# Vector_Mini_ST_2.net
KiCad netlist of a schematic drawn in Altium Designer
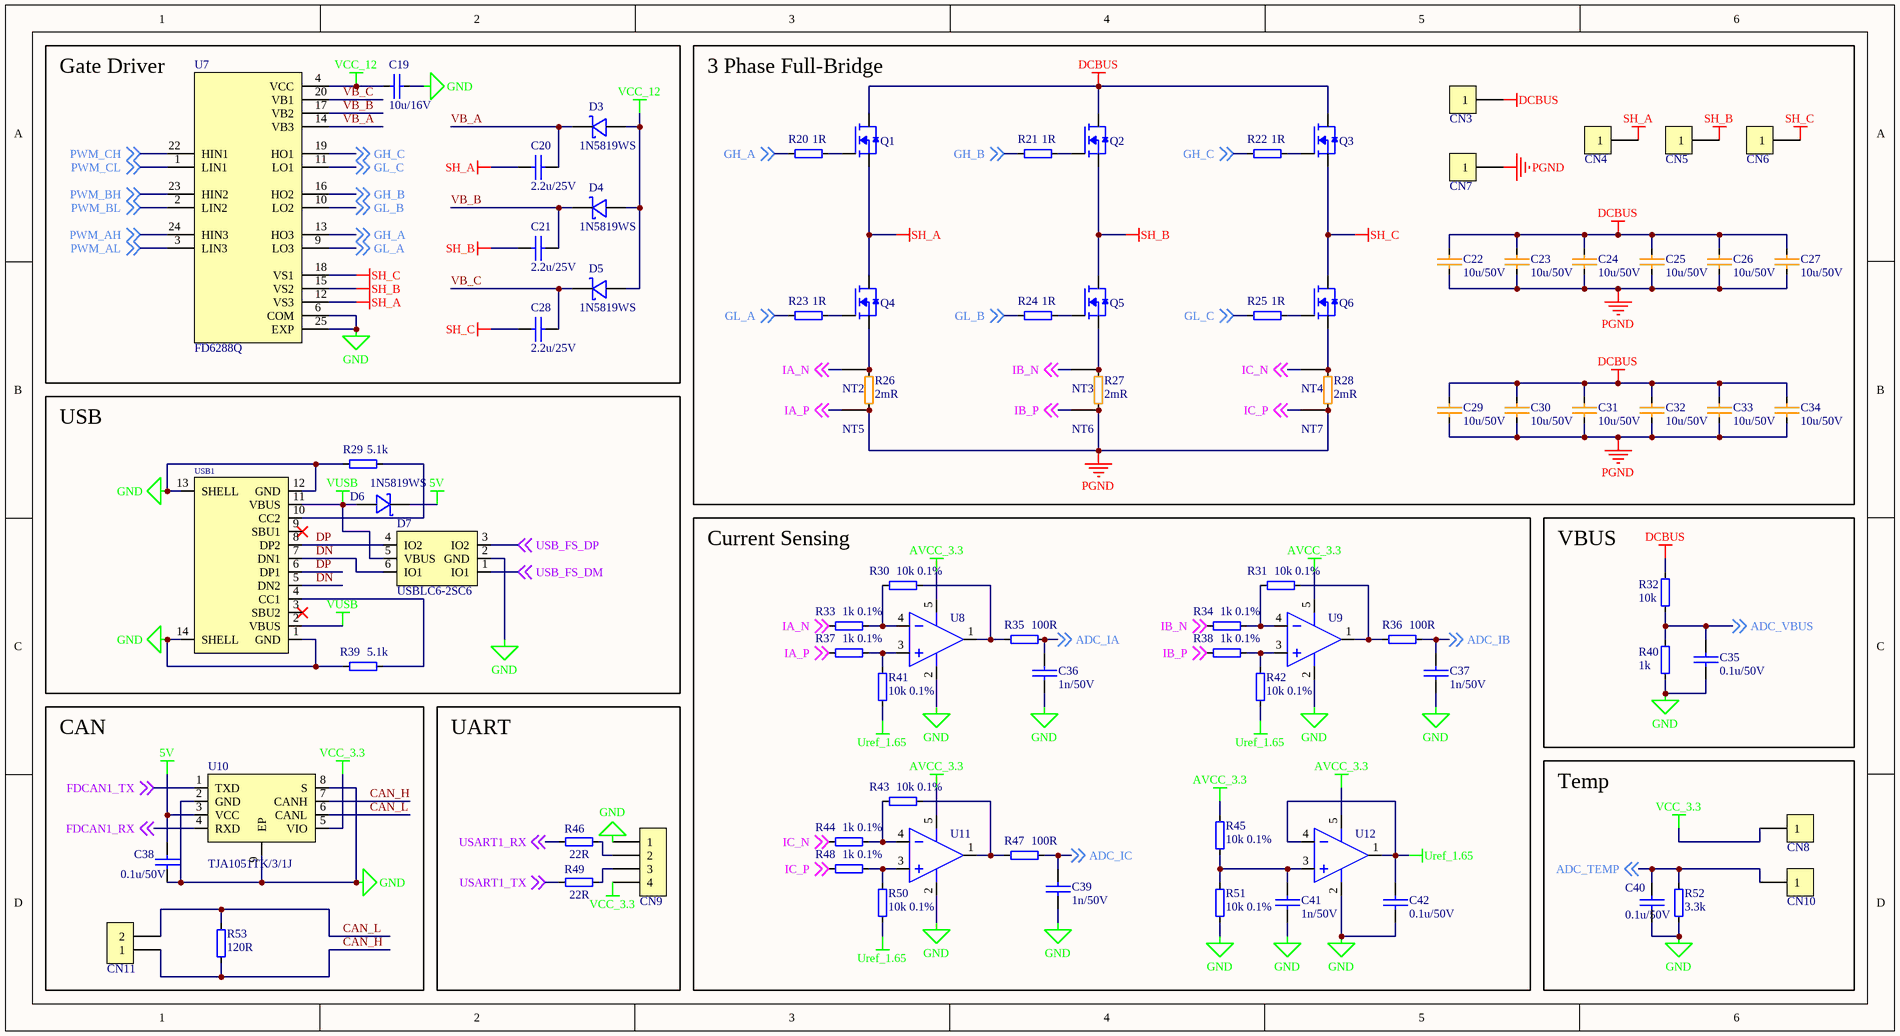
[diagram p0: Vector_Mini_ST_2.SchDoc]

(export (version "E")
  (design (tool "Eeschema 10.0.6"))
  (components
    (comp (ref "C19")
      (value "10u/16V")
      (footprint "C0603_S")
      (description "贴片电容")
      (libsource (lib "") (part "CAP_1"))
    )
    (comp (ref "C20")
      (value "2.2u/25V")
      (footprint "C0603_S")
      (description "贴片电容")
      (libsource (lib "Controller") (part "CAP"))
    )
    (comp (ref "C21")
      (value "2.2u/25V")
      (footprint "C0603_S")
      (description "贴片电容")
      (libsource (lib "Controller") (part "CAP"))
    )
    (comp (ref "C22")
      (value "10u/50V")
      (footprint "C1206_S")
      (description "1206贴片电容")
      (libsource (lib "Capacitor") (part "C1206"))
    )
    (comp (ref "C23")
      (value "10u/50V")
      (footprint "C1206_S")
      (description "1206贴片电容")
      (libsource (lib "Capacitor") (part "C1206"))
    )
    (comp (ref "C24")
      (value "10u/50V")
      (footprint "C1206_S")
      (description "1206贴片电容")
      (libsource (lib "Capacitor") (part "C1206"))
    )
    (comp (ref "C25")
      (value "10u/50V")
      (footprint "C1206_S")
      (description "1206贴片电容")
      (libsource (lib "Capacitor") (part "C1206"))
    )
    (comp (ref "C26")
      (value "10u/50V")
      (footprint "C1206_S")
      (description "1206贴片电容")
      (libsource (lib "Capacitor") (part "C1206"))
    )
    (comp (ref "C27")
      (value "10u/50V")
      (footprint "C1206_S")
      (description "1206贴片电容")
      (libsource (lib "Capacitor") (part "C1206"))
    )
    (comp (ref "C28")
      (value "2.2u/25V")
      (footprint "C0603_S")
      (description "贴片电容")
      (libsource (lib "Controller") (part "CAP"))
    )
    (comp (ref "C29")
      (value "10u/50V")
      (footprint "C1206_S")
      (description "1206贴片电容")
      (libsource (lib "Capacitor") (part "C1206"))
    )
    (comp (ref "C30")
      (value "10u/50V")
      (footprint "C1206_S")
      (description "1206贴片电容")
      (libsource (lib "Capacitor") (part "C1206"))
    )
    (comp (ref "C31")
      (value "10u/50V")
      (footprint "C1206_S")
      (description "1206贴片电容")
      (libsource (lib "Capacitor") (part "C1206"))
    )
    (comp (ref "C32")
      (value "10u/50V")
      (footprint "C1206_S")
      (description "1206贴片电容")
      (libsource (lib "Capacitor") (part "C1206"))
    )
    (comp (ref "C33")
      (value "10u/50V")
      (footprint "C1206_S")
      (description "1206贴片电容")
      (libsource (lib "Capacitor") (part "C1206"))
    )
    (comp (ref "C34")
      (value "10u/50V")
      (footprint "C1206_S")
      (description "1206贴片电容")
      (libsource (lib "Capacitor") (part "C1206"))
    )
    (comp (ref "C35")
      (value "0.1u/50V")
      (footprint "C0603_S")
      (description "贴片电容")
      (libsource (lib "Controller") (part "CAP"))
    )
    (comp (ref "C36")
      (value "1n/50V")
      (footprint "C0603_S")
      (description "贴片电容")
      (libsource (lib "Controller") (part "CAP"))
    )
    (comp (ref "C37")
      (value "1n/50V")
      (footprint "C0603_S")
      (description "贴片电容")
      (libsource (lib "Controller") (part "CAP"))
    )
    (comp (ref "C38")
      (value "0.1u/50V")
      (footprint "C0603_S")
      (description "贴片电容")
      (libsource (lib "Controller") (part "CAP"))
    )
    (comp (ref "C39")
      (value "1n/50V")
      (footprint "C0603_S")
      (description "贴片电容")
      (libsource (lib "Controller") (part "CAP"))
    )
    (comp (ref "C40")
      (value "0.1u/50V")
      (footprint "C0603_S")
      (description "贴片电容")
      (libsource (lib "Controller") (part "CAP"))
    )
    (comp (ref "C41")
      (value "1n/50V")
      (footprint "C0603_S")
      (description "贴片电容")
      (libsource (lib "Controller") (part "CAP"))
    )
    (comp (ref "C42")
      (value "0.1u/50V")
      (footprint "C0603_S")
      (description "贴片电容")
      (libsource (lib "Controller") (part "CAP"))
    )
    (comp (ref "CN3") (value "PAD 5*4") (footprint "PAD 5*4") (libsource (lib "Connector") (part "PAD 5*4")))
    (comp (ref "CN4") (value "PAD 5*4") (footprint "PAD 5*4") (libsource (lib "Connector") (part "PAD 5*4")))
    (comp (ref "CN5") (value "PAD 5*4") (footprint "PAD 5*4") (libsource (lib "Connector") (part "PAD 5*4")))
    (comp (ref "CN6") (value "PAD 5*4") (footprint "PAD 5*4") (libsource (lib "Connector") (part "PAD 5*4")))
    (comp (ref "CN7") (value "PAD 5*4") (footprint "PAD 5*4") (libsource (lib "Connector") (part "PAD 5*4")))
    (comp (ref "CN8") (value "PAD 1*1") (footprint "PAD 1*1") (libsource (lib "Connector") (part "PAD 1*1")))
    (comp (ref "CN9")
      (value "GH1.25-4P")
      (footprint "GH1.25-WS-4P")
      (libsource (lib "Controller") (part "GH1.25-4P"))
    )
    (comp (ref "CN10") (value "PAD 1*1") (footprint "PAD 1*1") (libsource (lib "Connector") (part "PAD 1*1")))
    (comp (ref "CN11")
      (value "GH1.25-2P")
      (footprint "GH1.25-WS-2P")
      (libsource (lib "Controller") (part "GH1.25-2P"))
    )
    (comp (ref "D3")
      (value "1N5819WS")
      (footprint "SOD-323")
      (description "肖特基二极管")
      (fields (field (name "MANUFACTURER") "Hottech(合科泰)"))
      (libsource (lib "Controller") (part "1N5819WS"))
    )
    (comp (ref "D4")
      (value "1N5819WS")
      (footprint "SOD-323")
      (description "肖特基二极管")
      (fields (field (name "MANUFACTURER") "Hottech(合科泰)"))
      (libsource (lib "Controller") (part "1N5819WS"))
    )
    (comp (ref "D5")
      (value "1N5819WS")
      (footprint "SOD-323")
      (description "肖特基二极管")
      (fields (field (name "MANUFACTURER") "Hottech(合科泰)"))
      (libsource (lib "Controller") (part "1N5819WS"))
    )
    (comp (ref "D6")
      (value "1N5819WS")
      (footprint "SOD-323")
      (description "肖特基二极管")
      (fields (field (name "MANUFACTURER") "Hottech(合科泰)"))
      (libsource (lib "Controller") (part "1N5819WS"))
    )
    (comp (ref "D7")
      (value "USBLC6-2SC6")
      (footprint "SOT-23-6")
      (description "USB 2.0高速接口的ESD保护")
      (libsource (lib "Controller") (part "USBLC6-2SC6"))
    )
    (comp (ref "NT2")
      (value "NetTie_6mil")
      (footprint "Nettie6mil")
      (libsource (lib "Connector") (part "NetTie_6mil"))
    )
    (comp (ref "NT3")
      (value "NetTie_6mil")
      (footprint "Nettie6mil")
      (libsource (lib "Connector") (part "NetTie_6mil"))
    )
    (comp (ref "NT4")
      (value "NetTie_6mil")
      (footprint "Nettie6mil")
      (libsource (lib "Connector") (part "NetTie_6mil"))
    )
    (comp (ref "NT5")
      (value "NetTie_6mil")
      (footprint "Nettie6mil")
      (libsource (lib "Connector") (part "NetTie_6mil"))
    )
    (comp (ref "NT6")
      (value "NetTie_6mil")
      (footprint "Nettie6mil")
      (libsource (lib "Connector") (part "NetTie_6mil"))
    )
    (comp (ref "NT7")
      (value "NetTie_6mil")
      (footprint "Nettie6mil")
      (libsource (lib "Connector") (part "NetTie_6mil"))
    )
    (comp (ref "Q1")
      (value "CSD18540Q5B")
      (footprint "VSON-8")
      (fields (field (name "MF") "Texas Instruments"))
      (libsource (lib "Transistor") (part "CSD18540Q5B"))
    )
    (comp (ref "Q2")
      (value "CSD18540Q5B")
      (footprint "VSON-8")
      (fields (field (name "MF") "Texas Instruments"))
      (libsource (lib "Transistor") (part "CSD18540Q5B"))
    )
    (comp (ref "Q3")
      (value "CSD18540Q5B")
      (footprint "VSON-8")
      (fields (field (name "MF") "Texas Instruments"))
      (libsource (lib "Transistor") (part "CSD18540Q5B"))
    )
    (comp (ref "Q4")
      (value "CSD18540Q5B")
      (footprint "VSON-8")
      (fields (field (name "MF") "Texas Instruments"))
      (libsource (lib "Transistor") (part "CSD18540Q5B"))
    )
    (comp (ref "Q5")
      (value "CSD18540Q5B")
      (footprint "VSON-8")
      (fields (field (name "MF") "Texas Instruments"))
      (libsource (lib "Transistor") (part "CSD18540Q5B"))
    )
    (comp (ref "Q6")
      (value "CSD18540Q5B")
      (footprint "VSON-8")
      (fields (field (name "MF") "Texas Instruments"))
      (libsource (lib "Transistor") (part "CSD18540Q5B"))
    )
    (comp (ref "R20")
      (value "1R")
      (footprint "R0603_S")
      (description "贴片电阻")
      (libsource (lib "Controller") (part "RES"))
    )
    (comp (ref "R21")
      (value "1R")
      (footprint "R0603_S")
      (description "贴片电阻")
      (libsource (lib "Controller") (part "RES"))
    )
    (comp (ref "R22")
      (value "1R")
      (footprint "R0603_S")
      (description "贴片电阻")
      (libsource (lib "Controller") (part "RES"))
    )
    (comp (ref "R23")
      (value "1R")
      (footprint "R0603_S")
      (description "贴片电阻")
      (libsource (lib "Controller") (part "RES"))
    )
    (comp (ref "R24")
      (value "1R")
      (footprint "R0603_S")
      (description "贴片电阻")
      (libsource (lib "Controller") (part "RES"))
    )
    (comp (ref "R25")
      (value "1R")
      (footprint "R0603_S")
      (description "贴片电阻")
      (libsource (lib "Controller") (part "RES"))
    )
    (comp (ref "R26")
      (value "2mR")
      (footprint "R2512_S")
      (description "2512贴片电阻")
      (libsource (lib "Resistor") (part "R2512"))
    )
    (comp (ref "R27")
      (value "2mR")
      (footprint "R2512_S")
      (description "2512贴片电阻")
      (libsource (lib "Resistor") (part "R2512"))
    )
    (comp (ref "R28")
      (value "2mR")
      (footprint "R2512_S")
      (description "2512贴片电阻")
      (libsource (lib "Resistor") (part "R2512"))
    )
    (comp (ref "R29")
      (value "5.1k")
      (footprint "R0603_S")
      (description "贴片电阻")
      (libsource (lib "Controller") (part "RES"))
    )
    (comp (ref "R30")
      (value "10k 0.1%")
      (footprint "R0603_S")
      (description "贴片电阻")
      (libsource (lib "Controller") (part "RES"))
    )
    (comp (ref "R31")
      (value "10k 0.1%")
      (footprint "R0603_S")
      (description "贴片电阻")
      (libsource (lib "Controller") (part "RES"))
    )
    (comp (ref "R32")
      (value "10k")
      (footprint "R0603_S")
      (description "贴片电阻")
      (libsource (lib "Controller") (part "RES"))
    )
    (comp (ref "R33")
      (value "1k 0.1%")
      (footprint "R0603_S")
      (description "贴片电阻")
      (libsource (lib "Controller") (part "RES"))
    )
    (comp (ref "R34")
      (value "1k 0.1%")
      (footprint "R0603_S")
      (description "贴片电阻")
      (libsource (lib "Controller") (part "RES"))
    )
    (comp (ref "R35")
      (value "100R")
      (footprint "R0603_S")
      (description "贴片电阻")
      (libsource (lib "Controller") (part "RES"))
    )
    (comp (ref "R36")
      (value "100R")
      (footprint "R0603_S")
      (description "贴片电阻")
      (libsource (lib "Controller") (part "RES"))
    )
    (comp (ref "R37")
      (value "1k 0.1%")
      (footprint "R0603_S")
      (description "贴片电阻")
      (libsource (lib "Controller") (part "RES"))
    )
    (comp (ref "R38")
      (value "1k 0.1%")
      (footprint "R0603_S")
      (description "贴片电阻")
      (libsource (lib "Controller") (part "RES"))
    )
    (comp (ref "R39")
      (value "5.1k")
      (footprint "R0603_S")
      (description "贴片电阻")
      (libsource (lib "Controller") (part "RES"))
    )
    (comp (ref "R40")
      (value "1k")
      (footprint "R0603_S")
      (description "贴片电阻")
      (libsource (lib "Controller") (part "RES"))
    )
    (comp (ref "R41")
      (value "10k 0.1%")
      (footprint "R0603_S")
      (description "贴片电阻")
      (libsource (lib "Controller") (part "RES"))
    )
    (comp (ref "R42")
      (value "10k 0.1%")
      (footprint "R0603_S")
      (description "贴片电阻")
      (libsource (lib "Controller") (part "RES"))
    )
    (comp (ref "R43")
      (value "10k 0.1%")
      (footprint "R0603_S")
      (description "贴片电阻")
      (libsource (lib "Controller") (part "RES"))
    )
    (comp (ref "R44")
      (value "1k 0.1%")
      (footprint "R0603_S")
      (description "贴片电阻")
      (libsource (lib "Controller") (part "RES"))
    )
    (comp (ref "R45")
      (value "10k 0.1%")
      (footprint "R0603_S")
      (description "贴片电阻")
      (libsource (lib "Controller") (part "RES"))
    )
    (comp (ref "R46")
      (value "22R")
      (footprint "R0603_S")
      (description "贴片电阻")
      (libsource (lib "Controller") (part "RES"))
    )
    (comp (ref "R47")
      (value "100R")
      (footprint "R0603_S")
      (description "贴片电阻")
      (libsource (lib "Controller") (part "RES"))
    )
    (comp (ref "R48")
      (value "1k 0.1%")
      (footprint "R0603_S")
      (description "贴片电阻")
      (libsource (lib "Controller") (part "RES"))
    )
    (comp (ref "R49")
      (value "22R")
      (footprint "R0603_S")
      (description "贴片电阻")
      (libsource (lib "Controller") (part "RES"))
    )
    (comp (ref "R50")
      (value "10k 0.1%")
      (footprint "R0603_S")
      (description "贴片电阻")
      (libsource (lib "Controller") (part "RES"))
    )
    (comp (ref "R51")
      (value "10k 0.1%")
      (footprint "R0603_S")
      (description "贴片电阻")
      (libsource (lib "Controller") (part "RES"))
    )
    (comp (ref "R52")
      (value "3.3k")
      (footprint "R0603_S")
      (description "贴片电阻")
      (libsource (lib "Controller") (part "RES"))
    )
    (comp (ref "R53")
      (value "120R")
      (footprint "R0603_S")
      (description "贴片电阻")
      (libsource (lib "Controller") (part "RES"))
    )
    (comp (ref "U7")
      (value "FD6288Q")
      (footprint "QFN-24")
      (description "三相栅极驱动")
      (fields (field (name "MF") "{'manufacturer': u'Fortior Tech'}"))
      (libsource (lib "Power Regulate") (part "FD6288Q"))
    )
    (comp (ref "U8") (value "RS721XF") (footprint "SOT-23-5") (libsource (lib "Amplifier") (part "RS721XF")))
    (comp (ref "U9") (value "RS721XF") (footprint "SOT-23-5") (libsource (lib "Amplifier") (part "RS721XF")))
    (comp (ref "U10")
      (value "TJA1051TK/3/1J")
      (footprint "VDFN-8")
      (fields (field (name "MANUFACTURER") "NXP(恩智浦)") (field (name "MANUFACTURER PART") "TJA1051T/1J"))
      (libsource (lib "Interface") (part "TJA1051TK/3/1J"))
    )
    (comp (ref "U11") (value "RS721XF") (footprint "SOT-23-5") (libsource (lib "Amplifier") (part "RS721XF")))
    (comp (ref "U12") (value "RS721XF") (footprint "SOT-23-5") (libsource (lib "Amplifier") (part "RS721XF")))
    (comp (ref "USB1")
      (value "TYPEC-WS-16P")
      (footprint "TYPEC-WS-16P")
      (fields
        (field (name "MANUFACTURER") "SHOU HAN(首韩)")
        (field (name "MANUFACTURER PART") "TYPE-C 16PIN 2MD(073)")
      )
      (libsource (lib "USB") (part "TYPEC-WS-16P"))
    )
  )
  (nets
    (net (code "1") (name "/CAN_H") (class "Default")
      (node (ref "CN11") (pin "1") (pinfunction "1_1") (pintype "passive"))
      (node (ref "R53") (pin "1") (pinfunction "1_1") (pintype "passive"))
      (node (ref "U10") (pin "7") (pinfunction "CANH_7") (pintype "passive"))
    )
    (net (code "2") (name "/CAN_L") (class "Default")
      (node (ref "CN11") (pin "2") (pinfunction "2_2") (pintype "passive"))
      (node (ref "R53") (pin "2") (pinfunction "2_2") (pintype "passive"))
      (node (ref "U10") (pin "6") (pinfunction "CANL_6") (pintype "passive"))
    )
    (net (code "3") (name "/DN") (class "Default")
      (node (ref "D7") (pin "6") (pinfunction "IO1_6") (pintype "passive"))
      (node (ref "USB1") (pin "5") (pinfunction "DN2_5") (pintype "passive"))
      (node (ref "USB1") (pin "7") (pinfunction "DN1_7") (pintype "passive"))
    )
    (net (code "4") (name "/DP") (class "Default")
      (node (ref "D7") (pin "4") (pinfunction "IO2_4") (pintype "passive"))
      (node (ref "USB1") (pin "6") (pinfunction "DP1_6") (pintype "passive"))
      (node (ref "USB1") (pin "8") (pinfunction "DP2_8") (pintype "passive"))
    )
    (net (code "5") (name "/VB_A") (class "Default")
      (node (ref "C20") (pin "2") (pinfunction "2_2") (pintype "passive"))
      (node (ref "D3") (pin "1") (pinfunction "K_1") (pintype "passive"))
      (node (ref "U7") (pin "14") (pinfunction "VB3_14") (pintype "passive"))
    )
    (net (code "6") (name "/VB_B") (class "Default")
      (node (ref "C21") (pin "2") (pinfunction "2_2") (pintype "passive"))
      (node (ref "D4") (pin "1") (pinfunction "K_1") (pintype "passive"))
      (node (ref "U7") (pin "17") (pinfunction "VB2_17") (pintype "passive"))
    )
    (net (code "7") (name "/VB_C") (class "Default")
      (node (ref "C28") (pin "2") (pinfunction "2_2") (pintype "passive"))
      (node (ref "D5") (pin "1") (pinfunction "K_1") (pintype "passive"))
      (node (ref "U7") (pin "20") (pinfunction "VB1_20") (pintype "passive"))
    )
    (net (code "8") (name "5V") (class "Default")
      (node (ref "C38") (pin "1") (pinfunction "1_1") (pintype "passive"))
      (node (ref "D6") (pin "1") (pinfunction "K_1") (pintype "passive"))
      (node (ref "U10") (pin "3") (pinfunction "VCC_3") (pintype "passive"))
    )
    (net (code "9") (name "ADC_IA") (class "Default")
      (node (ref "C36") (pin "2") (pinfunction "2_2") (pintype "passive"))
      (node (ref "R35") (pin "2") (pinfunction "2_2") (pintype "passive"))
    )
    (net (code "10") (name "ADC_IB") (class "Default")
      (node (ref "C37") (pin "2") (pinfunction "2_2") (pintype "passive"))
      (node (ref "R36") (pin "2") (pinfunction "2_2") (pintype "passive"))
    )
    (net (code "11") (name "ADC_IC") (class "Default")
      (node (ref "C39") (pin "2") (pinfunction "2_2") (pintype "passive"))
      (node (ref "R47") (pin "2") (pinfunction "2_2") (pintype "passive"))
    )
    (net (code "12") (name "ADC_TEMP") (class "Default")
      (node (ref "C40") (pin "1") (pinfunction "1_1") (pintype "passive"))
      (node (ref "CN10") (pin "1") (pinfunction "1_1") (pintype "passive"))
      (node (ref "R52") (pin "2") (pinfunction "2_2") (pintype "passive"))
    )
    (net (code "13") (name "ADC_VBUS") (class "Default")
      (node (ref "C35") (pin "2") (pinfunction "2_2") (pintype "passive"))
      (node (ref "R32") (pin "1") (pinfunction "1_1") (pintype "passive"))
      (node (ref "R40") (pin "2") (pinfunction "2_2") (pintype "passive"))
    )
    (net (code "14") (name "AVCC_3.3") (class "Default")
      (node (ref "R45") (pin "2") (pinfunction "2_2") (pintype "passive"))
      (node (ref "U11") (pin "5") (pinfunction "V+_5") (pintype "passive"))
      (node (ref "U12") (pin "5") (pinfunction "V+_5") (pintype "passive"))
      (node (ref "U8") (pin "5") (pinfunction "V+_5") (pintype "passive"))
      (node (ref "U9") (pin "5") (pinfunction "V+_5") (pintype "passive"))
    )
    (net (code "15") (name "DCBUS") (class "Default")
      (node (ref "C22") (pin "1") (pinfunction "1_1") (pintype "passive"))
      (node (ref "C23") (pin "1") (pinfunction "1_1") (pintype "passive"))
      (node (ref "C24") (pin "1") (pinfunction "1_1") (pintype "passive"))
      (node (ref "C25") (pin "1") (pinfunction "1_1") (pintype "passive"))
      (node (ref "C26") (pin "1") (pinfunction "1_1") (pintype "passive"))
      (node (ref "C27") (pin "1") (pinfunction "1_1") (pintype "passive"))
      (node (ref "C29") (pin "1") (pinfunction "1_1") (pintype "passive"))
      (node (ref "C30") (pin "1") (pinfunction "1_1") (pintype "passive"))
      (node (ref "C31") (pin "1") (pinfunction "1_1") (pintype "passive"))
      (node (ref "C32") (pin "1") (pinfunction "1_1") (pintype "passive"))
      (node (ref "C33") (pin "1") (pinfunction "1_1") (pintype "passive"))
      (node (ref "C34") (pin "1") (pinfunction "1_1") (pintype "passive"))
      (node (ref "CN3") (pin "1") (pinfunction "1_1") (pintype "passive"))
      (node (ref "Q1") (pin "3") (pinfunction "D_3") (pintype "passive"))
      (node (ref "Q2") (pin "3") (pinfunction "D_3") (pintype "passive"))
      (node (ref "Q3") (pin "3") (pinfunction "D_3") (pintype "passive"))
      (node (ref "R32") (pin "2") (pinfunction "2_2") (pintype "passive"))
    )
    (net (code "16") (name "FDCAN1_RX") (class "Default")
      (node (ref "U10") (pin "4") (pinfunction "RXD_4") (pintype "passive"))
    )
    (net (code "17") (name "FDCAN1_TX") (class "Default")
      (node (ref "U10") (pin "1") (pinfunction "TXD_1") (pintype "passive"))
    )
    (net (code "18") (name "GH_A") (class "Default")
      (node (ref "R20") (pin "1") (pinfunction "1_1") (pintype "passive"))
      (node (ref "U7") (pin "13") (pinfunction "HO3_13") (pintype "passive"))
    )
    (net (code "19") (name "GH_B") (class "Default")
      (node (ref "R21") (pin "1") (pinfunction "1_1") (pintype "passive"))
      (node (ref "U7") (pin "16") (pinfunction "HO2_16") (pintype "passive"))
    )
    (net (code "20") (name "GH_C") (class "Default")
      (node (ref "R22") (pin "1") (pinfunction "1_1") (pintype "passive"))
      (node (ref "U7") (pin "19") (pinfunction "HO1_19") (pintype "passive"))
    )
    (net (code "21") (name "GL_A") (class "Default")
      (node (ref "R23") (pin "1") (pinfunction "1_1") (pintype "passive"))
      (node (ref "U7") (pin "9") (pinfunction "LO3_9") (pintype "passive"))
    )
    (net (code "22") (name "GL_B") (class "Default")
      (node (ref "R24") (pin "1") (pinfunction "1_1") (pintype "passive"))
      (node (ref "U7") (pin "10") (pinfunction "LO2_10") (pintype "passive"))
    )
    (net (code "23") (name "GL_C") (class "Default")
      (node (ref "R25") (pin "1") (pinfunction "1_1") (pintype "passive"))
      (node (ref "U7") (pin "11") (pinfunction "LO1_11") (pintype "passive"))
    )
    (net (code "24") (name "GND") (class "Default")
      (node (ref "C19") (pin "2") (pinfunction "2_2") (pintype "passive"))
      (node (ref "C35") (pin "1") (pinfunction "1_1") (pintype "passive"))
      (node (ref "C36") (pin "1") (pinfunction "1_1") (pintype "passive"))
      (node (ref "C37") (pin "1") (pinfunction "1_1") (pintype "passive"))
      (node (ref "C38") (pin "2") (pinfunction "2_2") (pintype "passive"))
      (node (ref "C39") (pin "1") (pinfunction "1_1") (pintype "passive"))
      (node (ref "C40") (pin "2") (pinfunction "2_2") (pintype "passive"))
      (node (ref "C41") (pin "1") (pinfunction "1_1") (pintype "passive"))
      (node (ref "C42") (pin "1") (pinfunction "1_1") (pintype "passive"))
      (node (ref "CN9") (pin "1") (pinfunction "1_1") (pintype "passive"))
      (node (ref "D7") (pin "2") (pinfunction "GND_2") (pintype "passive"))
      (node (ref "R29") (pin "1") (pinfunction "1_1") (pintype "passive"))
      (node (ref "R39") (pin "1") (pinfunction "1_1") (pintype "passive"))
      (node (ref "R40") (pin "1") (pinfunction "1_1") (pintype "passive"))
      (node (ref "R51") (pin "1") (pinfunction "1_1") (pintype "passive"))
      (node (ref "R52") (pin "1") (pinfunction "1_1") (pintype "passive"))
      (node (ref "U10") (pin "2") (pinfunction "GND_2") (pintype "passive"))
      (node (ref "U10") (pin "8") (pinfunction "S_8") (pintype "passive"))
      (node (ref "U10") (pin "9") (pinfunction "EP_9") (pintype "passive"))
      (node (ref "U11") (pin "2") (pinfunction "V-_2") (pintype "passive"))
      (node (ref "U12") (pin "2") (pinfunction "V-_2") (pintype "passive"))
      (node (ref "U7") (pin "25") (pinfunction "EXP_25") (pintype "passive"))
      (node (ref "U7") (pin "6") (pinfunction "COM_6") (pintype "passive"))
      (node (ref "U8") (pin "2") (pinfunction "V-_2") (pintype "passive"))
      (node (ref "U9") (pin "2") (pinfunction "V-_2") (pintype "passive"))
      (node (ref "USB1") (pin "1") (pinfunction "GND_1") (pintype "passive"))
      (node (ref "USB1") (pin "12") (pinfunction "GND_12") (pintype "passive"))
      (node (ref "USB1") (pin "13") (pinfunction "SHELL_13") (pintype "passive"))
      (node (ref "USB1") (pin "14") (pinfunction "SHELL_14") (pintype "passive"))
    )
    (net (code "25") (name "IA_N") (class "Default")
      (node (ref "NT2") (pin "1") (pintype "passive"))
      (node (ref "R33") (pin "1") (pinfunction "1_1") (pintype "passive"))
    )
    (net (code "26") (name "IA_P") (class "Default")
      (node (ref "NT5") (pin "1") (pintype "passive"))
      (node (ref "R37") (pin "1") (pinfunction "1_1") (pintype "passive"))
    )
    (net (code "27") (name "IB_N") (class "Default")
      (node (ref "NT3") (pin "1") (pintype "passive"))
      (node (ref "R34") (pin "1") (pinfunction "1_1") (pintype "passive"))
    )
    (net (code "28") (name "IB_P") (class "Default")
      (node (ref "NT6") (pin "1") (pintype "passive"))
      (node (ref "R38") (pin "1") (pinfunction "1_1") (pintype "passive"))
    )
    (net (code "29") (name "IC_N") (class "Default")
      (node (ref "NT4") (pin "1") (pintype "passive"))
      (node (ref "R44") (pin "1") (pinfunction "1_1") (pintype "passive"))
    )
    (net (code "30") (name "IC_P") (class "Default")
      (node (ref "NT7") (pin "1") (pintype "passive"))
      (node (ref "R48") (pin "1") (pinfunction "1_1") (pintype "passive"))
    )
    (net (code "31") (name "Net-(CN9-Pad2)") (class "Default")
      (node (ref "CN9") (pin "2") (pinfunction "2_2") (pintype "passive"))
      (node (ref "R46") (pin "2") (pinfunction "2_2") (pintype "passive"))
    )
    (net (code "32") (name "Net-(CN9-Pad3)") (class "Default")
      (node (ref "CN9") (pin "3") (pinfunction "3_3") (pintype "passive"))
      (node (ref "R49") (pin "2") (pinfunction "2_2") (pintype "passive"))
    )
    (net (code "33") (name "Net-(Q1-G)") (class "Default")
      (node (ref "Q1") (pin "2") (pinfunction "G_2") (pintype "passive"))
      (node (ref "R20") (pin "2") (pinfunction "2_2") (pintype "passive"))
    )
    (net (code "34") (name "Net-(Q2-G)") (class "Default")
      (node (ref "Q2") (pin "2") (pinfunction "G_2") (pintype "passive"))
      (node (ref "R21") (pin "2") (pinfunction "2_2") (pintype "passive"))
    )
    (net (code "35") (name "Net-(Q3-G)") (class "Default")
      (node (ref "Q3") (pin "2") (pinfunction "G_2") (pintype "passive"))
      (node (ref "R22") (pin "2") (pinfunction "2_2") (pintype "passive"))
    )
    (net (code "36") (name "Net-(Q4-G)") (class "Default")
      (node (ref "Q4") (pin "2") (pinfunction "G_2") (pintype "passive"))
      (node (ref "R23") (pin "2") (pinfunction "2_2") (pintype "passive"))
    )
    (net (code "37") (name "Net-(Q4-S)") (class "Default")
      (node (ref "NT2") (pin "2") (pinfunction "2_2") (pintype "passive"))
      (node (ref "Q4") (pin "1") (pinfunction "S_1") (pintype "passive"))
      (node (ref "R26") (pin "2") (pinfunction "2_2") (pintype "passive"))
    )
    (net (code "38") (name "Net-(Q5-G)") (class "Default")
      (node (ref "Q5") (pin "2") (pinfunction "G_2") (pintype "passive"))
      (node (ref "R24") (pin "2") (pinfunction "2_2") (pintype "passive"))
    )
    (net (code "39") (name "Net-(Q5-S)") (class "Default")
      (node (ref "NT3") (pin "2") (pinfunction "2_2") (pintype "passive"))
      (node (ref "Q5") (pin "1") (pinfunction "S_1") (pintype "passive"))
      (node (ref "R27") (pin "2") (pinfunction "2_2") (pintype "passive"))
    )
    (net (code "40") (name "Net-(Q6-G)") (class "Default")
      (node (ref "Q6") (pin "2") (pinfunction "G_2") (pintype "passive"))
      (node (ref "R25") (pin "2") (pinfunction "2_2") (pintype "passive"))
    )
    (net (code "41") (name "Net-(Q6-S)") (class "Default")
      (node (ref "NT4") (pin "2") (pinfunction "2_2") (pintype "passive"))
      (node (ref "Q6") (pin "1") (pinfunction "S_1") (pintype "passive"))
      (node (ref "R28") (pin "2") (pinfunction "2_2") (pintype "passive"))
    )
    (net (code "42") (name "Net-(U8-+IN)") (class "Default")
      (node (ref "R37") (pin "2") (pinfunction "2_2") (pintype "passive"))
      (node (ref "R41") (pin "2") (pinfunction "2_2") (pintype "passive"))
      (node (ref "U8") (pin "3") (pinfunction "+IN_3") (pintype "passive"))
    )
    (net (code "43") (name "Net-(U8--IN)") (class "Default")
      (node (ref "R30") (pin "1") (pinfunction "1_1") (pintype "passive"))
      (node (ref "R33") (pin "2") (pinfunction "2_2") (pintype "passive"))
      (node (ref "U8") (pin "4") (pinfunction "-IN_4") (pintype "passive"))
    )
    (net (code "44") (name "Net-(U8-OUT)") (class "Default")
      (node (ref "R30") (pin "2") (pinfunction "2_2") (pintype "passive"))
      (node (ref "R35") (pin "1") (pinfunction "1_1") (pintype "passive"))
      (node (ref "U8") (pin "1") (pinfunction "OUT_1") (pintype "passive"))
    )
    (net (code "45") (name "Net-(U9-+IN)") (class "Default")
      (node (ref "R38") (pin "2") (pinfunction "2_2") (pintype "passive"))
      (node (ref "R42") (pin "2") (pinfunction "2_2") (pintype "passive"))
      (node (ref "U9") (pin "3") (pinfunction "+IN_3") (pintype "passive"))
    )
    (net (code "46") (name "Net-(U9--IN)") (class "Default")
      (node (ref "R31") (pin "1") (pinfunction "1_1") (pintype "passive"))
      (node (ref "R34") (pin "2") (pinfunction "2_2") (pintype "passive"))
      (node (ref "U9") (pin "4") (pinfunction "-IN_4") (pintype "passive"))
    )
    (net (code "47") (name "Net-(U9-OUT)") (class "Default")
      (node (ref "R31") (pin "2") (pinfunction "2_2") (pintype "passive"))
      (node (ref "R36") (pin "1") (pinfunction "1_1") (pintype "passive"))
      (node (ref "U9") (pin "1") (pinfunction "OUT_1") (pintype "passive"))
    )
    (net (code "48") (name "Net-(U11-+IN)") (class "Default")
      (node (ref "R48") (pin "2") (pinfunction "2_2") (pintype "passive"))
      (node (ref "R50") (pin "2") (pinfunction "2_2") (pintype "passive"))
      (node (ref "U11") (pin "3") (pinfunction "+IN_3") (pintype "passive"))
    )
    (net (code "49") (name "Net-(U11--IN)") (class "Default")
      (node (ref "R43") (pin "1") (pinfunction "1_1") (pintype "passive"))
      (node (ref "R44") (pin "2") (pinfunction "2_2") (pintype "passive"))
      (node (ref "U11") (pin "4") (pinfunction "-IN_4") (pintype "passive"))
    )
    (net (code "50") (name "Net-(U11-OUT)") (class "Default")
      (node (ref "R43") (pin "2") (pinfunction "2_2") (pintype "passive"))
      (node (ref "R47") (pin "1") (pinfunction "1_1") (pintype "passive"))
      (node (ref "U11") (pin "1") (pinfunction "OUT_1") (pintype "passive"))
    )
    (net (code "51") (name "Net-(U12-+IN)") (class "Default")
      (node (ref "C41") (pin "2") (pinfunction "2_2") (pintype "passive"))
      (node (ref "R45") (pin "1") (pinfunction "1_1") (pintype "passive"))
      (node (ref "R51") (pin "2") (pinfunction "2_2") (pintype "passive"))
      (node (ref "U12") (pin "3") (pinfunction "+IN_3") (pintype "passive"))
    )
    (net (code "52") (name "Net-(USB1-CC1)") (class "Default")
      (node (ref "R39") (pin "2") (pinfunction "2_2") (pintype "passive"))
      (node (ref "USB1") (pin "4") (pinfunction "CC1_4") (pintype "passive"))
    )
    (net (code "53") (name "Net-(USB1-CC2)") (class "Default")
      (node (ref "R29") (pin "2") (pinfunction "2_2") (pintype "passive"))
      (node (ref "USB1") (pin "10") (pinfunction "CC2_10") (pintype "passive"))
    )
    (net (code "54") (name "PGND") (class "Default")
      (node (ref "C22") (pin "2") (pinfunction "2_2") (pintype "passive"))
      (node (ref "C23") (pin "2") (pinfunction "2_2") (pintype "passive"))
      (node (ref "C24") (pin "2") (pinfunction "2_2") (pintype "passive"))
      (node (ref "C25") (pin "2") (pinfunction "2_2") (pintype "passive"))
      (node (ref "C26") (pin "2") (pinfunction "2_2") (pintype "passive"))
      (node (ref "C27") (pin "2") (pinfunction "2_2") (pintype "passive"))
      (node (ref "C29") (pin "2") (pinfunction "2_2") (pintype "passive"))
      (node (ref "C30") (pin "2") (pinfunction "2_2") (pintype "passive"))
      (node (ref "C31") (pin "2") (pinfunction "2_2") (pintype "passive"))
      (node (ref "C32") (pin "2") (pinfunction "2_2") (pintype "passive"))
      (node (ref "C33") (pin "2") (pinfunction "2_2") (pintype "passive"))
      (node (ref "C34") (pin "2") (pinfunction "2_2") (pintype "passive"))
      (node (ref "CN7") (pin "1") (pinfunction "1_1") (pintype "passive"))
      (node (ref "NT5") (pin "2") (pinfunction "2_2") (pintype "passive"))
      (node (ref "NT6") (pin "2") (pinfunction "2_2") (pintype "passive"))
      (node (ref "NT7") (pin "2") (pinfunction "2_2") (pintype "passive"))
      (node (ref "R26") (pin "1") (pinfunction "1_1") (pintype "passive"))
      (node (ref "R27") (pin "1") (pinfunction "1_1") (pintype "passive"))
      (node (ref "R28") (pin "1") (pinfunction "1_1") (pintype "passive"))
    )
    (net (code "55") (name "PWM_AH") (class "Default")
      (node (ref "U7") (pin "24") (pinfunction "HIN3_24") (pintype "passive"))
    )
    (net (code "56") (name "PWM_AL") (class "Default")
      (node (ref "U7") (pin "3") (pinfunction "LIN3_3") (pintype "passive"))
    )
    (net (code "57") (name "PWM_BH") (class "Default")
      (node (ref "U7") (pin "23") (pinfunction "HIN2_23") (pintype "passive"))
    )
    (net (code "58") (name "PWM_BL") (class "Default")
      (node (ref "U7") (pin "2") (pinfunction "LIN2_2") (pintype "passive"))
    )
    (net (code "59") (name "PWM_CH") (class "Default")
      (node (ref "U7") (pin "22") (pinfunction "HIN1_22") (pintype "passive"))
    )
    (net (code "60") (name "PWM_CL") (class "Default")
      (node (ref "U7") (pin "1") (pinfunction "LIN1_1") (pintype "passive"))
    )
    (net (code "61") (name "SH_A") (class "Default")
      (node (ref "C20") (pin "1") (pinfunction "1_1") (pintype "passive"))
      (node (ref "CN4") (pin "1") (pinfunction "1_1") (pintype "passive"))
      (node (ref "Q1") (pin "1") (pinfunction "S_1") (pintype "passive"))
      (node (ref "Q4") (pin "3") (pinfunction "D_3") (pintype "passive"))
      (node (ref "U7") (pin "12") (pinfunction "VS3_12") (pintype "passive"))
    )
    (net (code "62") (name "SH_B") (class "Default")
      (node (ref "C21") (pin "1") (pinfunction "1_1") (pintype "passive"))
      (node (ref "CN5") (pin "1") (pinfunction "1_1") (pintype "passive"))
      (node (ref "Q2") (pin "1") (pinfunction "S_1") (pintype "passive"))
      (node (ref "Q5") (pin "3") (pinfunction "D_3") (pintype "passive"))
      (node (ref "U7") (pin "15") (pinfunction "VS2_15") (pintype "passive"))
    )
    (net (code "63") (name "SH_C") (class "Default")
      (node (ref "C28") (pin "1") (pinfunction "1_1") (pintype "passive"))
      (node (ref "CN6") (pin "1") (pinfunction "1_1") (pintype "passive"))
      (node (ref "Q3") (pin "1") (pinfunction "S_1") (pintype "passive"))
      (node (ref "Q6") (pin "3") (pinfunction "D_3") (pintype "passive"))
      (node (ref "U7") (pin "18") (pinfunction "VS1_18") (pintype "passive"))
    )
    (net (code "64") (name "USART1_RX") (class "Default")
      (node (ref "R46") (pin "1") (pinfunction "1_1") (pintype "passive"))
    )
    (net (code "65") (name "USART1_TX") (class "Default")
      (node (ref "R49") (pin "1") (pinfunction "1_1") (pintype "passive"))
    )
    (net (code "66") (name "USB_FS_DM") (class "Default")
      (node (ref "D7") (pin "1") (pinfunction "IO1_1") (pintype "passive"))
    )
    (net (code "67") (name "USB_FS_DP") (class "Default")
      (node (ref "D7") (pin "3") (pinfunction "IO2_3") (pintype "passive"))
    )
    (net (code "68") (name "Uref_1.65") (class "Default")
      (node (ref "C42") (pin "2") (pinfunction "2_2") (pintype "passive"))
      (node (ref "R41") (pin "1") (pinfunction "1_1") (pintype "passive"))
      (node (ref "R42") (pin "1") (pinfunction "1_1") (pintype "passive"))
      (node (ref "R50") (pin "1") (pinfunction "1_1") (pintype "passive"))
      (node (ref "U12") (pin "1") (pinfunction "OUT_1") (pintype "passive"))
      (node (ref "U12") (pin "4") (pinfunction "-IN_4") (pintype "passive"))
    )
    (net (code "69") (name "VCC_3.3") (class "Default")
      (node (ref "CN8") (pin "1") (pinfunction "1_1") (pintype "passive"))
      (node (ref "CN9") (pin "4") (pinfunction "4_4") (pintype "passive"))
      (node (ref "U10") (pin "5") (pinfunction "VIO_5") (pintype "passive"))
    )
    (net (code "70") (name "VCC_12") (class "Default")
      (node (ref "C19") (pin "1") (pinfunction "1_1") (pintype "passive"))
      (node (ref "D3") (pin "2") (pinfunction "A_2") (pintype "passive"))
      (node (ref "D4") (pin "2") (pinfunction "A_2") (pintype "passive"))
      (node (ref "D5") (pin "2") (pinfunction "A_2") (pintype "passive"))
      (node (ref "U7") (pin "4") (pinfunction "VCC_4") (pintype "passive"))
    )
    (net (code "71") (name "VUSB") (class "Default")
      (node (ref "D6") (pin "2") (pinfunction "A_2") (pintype "passive"))
      (node (ref "D7") (pin "5") (pinfunction "VBUS_5") (pintype "passive"))
      (node (ref "USB1") (pin "11") (pinfunction "VBUS_11") (pintype "passive"))
      (node (ref "USB1") (pin "2") (pinfunction "VBUS_2") (pintype "passive"))
    )
    (net (code "72") (name "unconnected-(USB1-SBU1-Pad9)") (class "Default")
      (node (ref "USB1") (pin "9") (pinfunction "SBU1_9") (pintype "passive+no_connect"))
    )
    (net (code "73") (name "unconnected-(USB1-SBU2-Pad3)") (class "Default")
      (node (ref "USB1") (pin "3") (pinfunction "SBU2_3") (pintype "passive+no_connect"))
    )
  )
)
